# PDM_v1.net
KiCad netlist of a schematic drawn in EAGLE
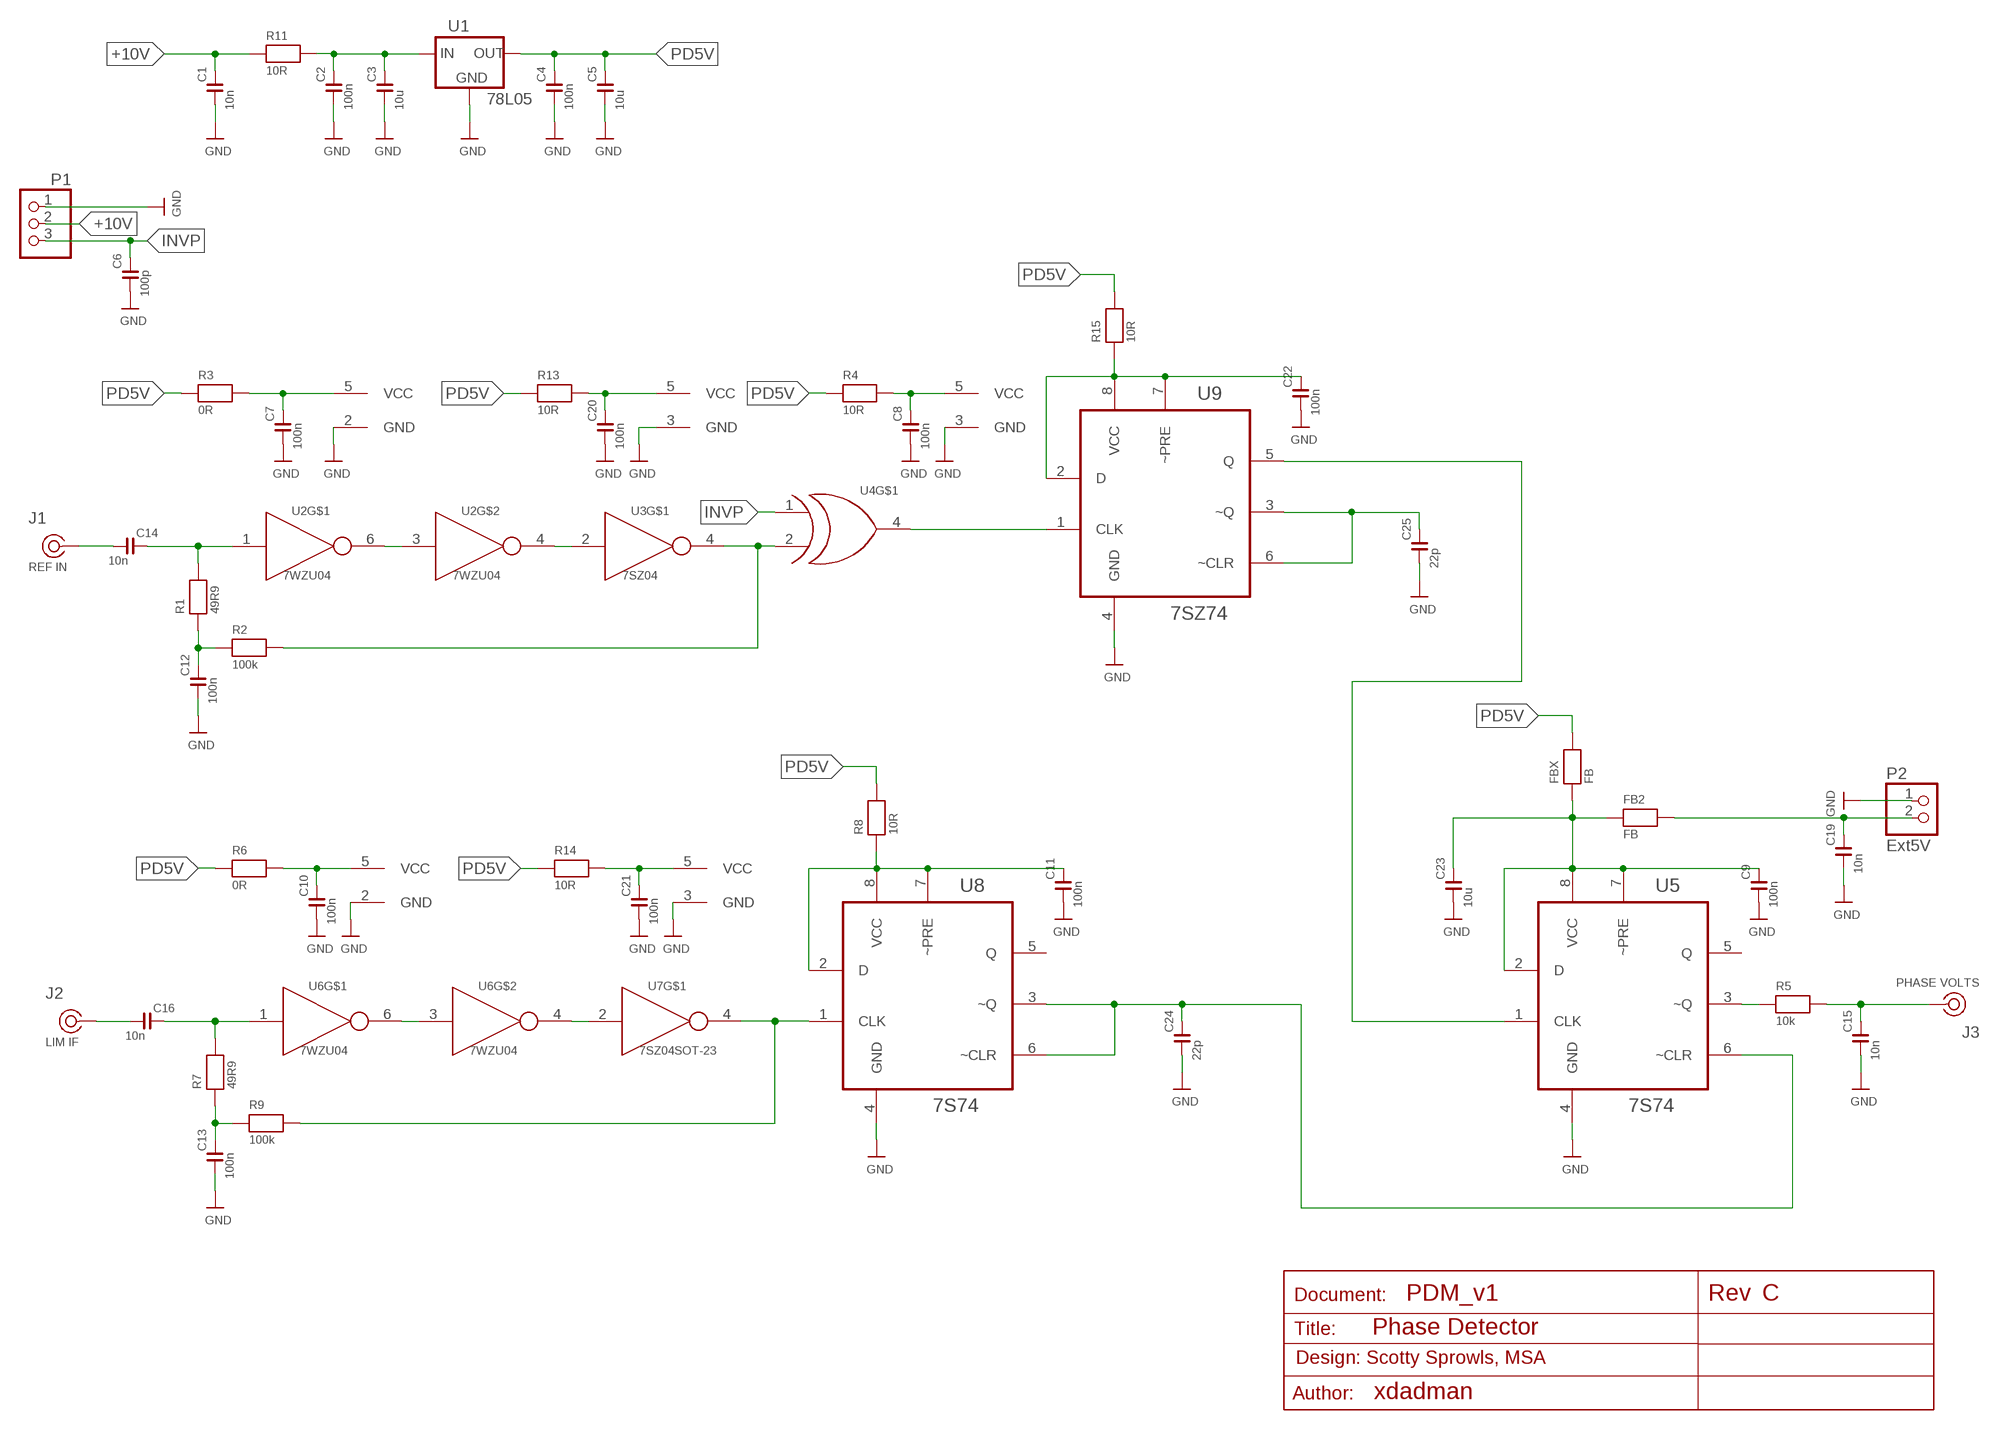
[diagram p0: schematic, sheet 1]

(export (version "E")
  (design (tool "Eeschema 10.0.6"))
  (components
    (comp (ref "C1")
      (value "10n")
      (footprint "eagle-import:C0805")
      (libsource (lib "eagle-import") (part "C080510N"))
    )
    (comp (ref "C2")
      (value "100n")
      (footprint "eagle-import:C0805")
      (libsource (lib "eagle-import") (part "C0805100N"))
    )
    (comp (ref "C3")
      (value "10u")
      (footprint "eagle-import:C1206")
      (libsource (lib "eagle-import") (part "CC120610U"))
    )
    (comp (ref "C4")
      (value "100n")
      (footprint "eagle-import:C0805")
      (libsource (lib "eagle-import") (part "C0805100N"))
    )
    (comp (ref "C5")
      (value "10u")
      (footprint "eagle-import:C1206")
      (libsource (lib "eagle-import") (part "CC120610U"))
    )
    (comp (ref "C6")
      (value "100p")
      (footprint "eagle-import:C0805")
      (libsource (lib "eagle-import") (part "C0805100P"))
    )
    (comp (ref "C7")
      (value "100n")
      (footprint "eagle-import:C0805")
      (libsource (lib "eagle-import") (part "C0805100N"))
    )
    (comp (ref "C8")
      (value "100n")
      (footprint "eagle-import:C0805")
      (libsource (lib "eagle-import") (part "C0805100N"))
    )
    (comp (ref "C9")
      (value "100n")
      (footprint "eagle-import:C0805")
      (libsource (lib "eagle-import") (part "C0805100N"))
    )
    (comp (ref "C10")
      (value "100n")
      (footprint "eagle-import:C0805")
      (libsource (lib "eagle-import") (part "C0805100N"))
    )
    (comp (ref "C11")
      (value "100n")
      (footprint "eagle-import:C0805")
      (libsource (lib "eagle-import") (part "C0805100N"))
    )
    (comp (ref "C12")
      (value "100n")
      (footprint "eagle-import:C0805")
      (libsource (lib "eagle-import") (part "C0805100N"))
    )
    (comp (ref "C13")
      (value "100n")
      (footprint "eagle-import:C0805")
      (libsource (lib "eagle-import") (part "C0805100N"))
    )
    (comp (ref "C14")
      (value "10n")
      (footprint "eagle-import:C0805")
      (libsource (lib "eagle-import") (part "C080510N"))
    )
    (comp (ref "C15")
      (value "10n")
      (footprint "eagle-import:C0805")
      (libsource (lib "eagle-import") (part "C080510N"))
    )
    (comp (ref "C16")
      (value "10n")
      (footprint "eagle-import:C0805")
      (libsource (lib "eagle-import") (part "C080510N"))
    )
    (comp (ref "C19")
      (value "10n")
      (footprint "eagle-import:C0805")
      (libsource (lib "eagle-import") (part "C080510N"))
    )
    (comp (ref "C20")
      (value "100n")
      (footprint "eagle-import:C0805")
      (libsource (lib "eagle-import") (part "C0805100N"))
    )
    (comp (ref "C21")
      (value "100n")
      (footprint "eagle-import:C0805")
      (libsource (lib "eagle-import") (part "C0805100N"))
    )
    (comp (ref "C22")
      (value "100n")
      (footprint "eagle-import:C0805")
      (libsource (lib "eagle-import") (part "C0805100N"))
    )
    (comp (ref "C23")
      (value "10u")
      (footprint "eagle-import:C1206")
      (libsource (lib "eagle-import") (part "CC120610U"))
    )
    (comp (ref "C24")
      (value "22p")
      (footprint "eagle-import:C0603")
      (libsource (lib "eagle-import") (part "CC060322P"))
    )
    (comp (ref "C25")
      (value "22p")
      (footprint "eagle-import:C0603")
      (libsource (lib "eagle-import") (part "CC060322P"))
    )
    (comp (ref "FB2")
      (value "FB")
      (footprint "eagle-import:R0805")
      (libsource (lib "eagle-import") (part "R0805FB045"))
    )
    (comp (ref "FBX")
      (value "FB")
      (footprint "eagle-import:R0805")
      (libsource (lib "eagle-import") (part "R0805FB045"))
    )
    (comp (ref "J1")
      (value "REF IN")
      (footprint "eagle-import:SLIM_COAX_PAD")
      (libsource (lib "eagle-import") (part "COAX"))
    )
    (comp (ref "J2")
      (value "LIM IF")
      (footprint "eagle-import:SLIM_COAX_PAD")
      (libsource (lib "eagle-import") (part "COAX"))
    )
    (comp (ref "J3")
      (value "PHASE VOLTS")
      (footprint "eagle-import:SLIM_COAX_PAD")
      (libsource (lib "eagle-import") (part "COAX"))
    )
    (comp (ref "P1")
      (value "PINHD-1X3")
      (footprint "eagle-import:1X03")
      (libsource (lib "eagle-import") (part "PINHD-1X3"))
    )
    (comp (ref "P2")
      (value "Ext5V")
      (footprint "eagle-import:1X02")
      (libsource (lib "eagle-import") (part "PINHD-1X2"))
    )
    (comp (ref "R1")
      (value "49R9")
      (footprint "eagle-import:R0805")
      (libsource (lib "eagle-import") (part "R080549R9"))
    )
    (comp (ref "R2")
      (value "100k")
      (footprint "eagle-import:R0805")
      (libsource (lib "eagle-import") (part "R0805100K"))
    )
    (comp (ref "R3")
      (value "0R")
      (footprint "eagle-import:R0805")
      (libsource (lib "eagle-import") (part "R08050R"))
    )
    (comp (ref "R4")
      (value "10R")
      (footprint "eagle-import:R0805")
      (libsource (lib "eagle-import") (part "R080510R"))
    )
    (comp (ref "R5")
      (value "10k")
      (footprint "eagle-import:R0805")
      (libsource (lib "eagle-import") (part "R080510K"))
    )
    (comp (ref "R6")
      (value "0R")
      (footprint "eagle-import:R0805")
      (libsource (lib "eagle-import") (part "R08050R"))
    )
    (comp (ref "R7")
      (value "49R9")
      (footprint "eagle-import:R0805")
      (libsource (lib "eagle-import") (part "R080549R9"))
    )
    (comp (ref "R8")
      (value "10R")
      (footprint "eagle-import:R0805")
      (libsource (lib "eagle-import") (part "R080510R"))
    )
    (comp (ref "R9")
      (value "100k")
      (footprint "eagle-import:R0805")
      (libsource (lib "eagle-import") (part "R0805100K"))
    )
    (comp (ref "R11")
      (value "10R")
      (footprint "eagle-import:R0805")
      (libsource (lib "eagle-import") (part "R080510R"))
    )
    (comp (ref "R13")
      (value "10R")
      (footprint "eagle-import:R0805")
      (libsource (lib "eagle-import") (part "R080510R"))
    )
    (comp (ref "R14")
      (value "10R")
      (footprint "eagle-import:R0805")
      (libsource (lib "eagle-import") (part "R080510R"))
    )
    (comp (ref "R15")
      (value "10R")
      (footprint "eagle-import:R0805")
      (libsource (lib "eagle-import") (part "R080510R"))
    )
    (comp (ref "U1")
      (value "78L05")
      (footprint "eagle-import:SOT89")
      (libsource (lib "eagle-import") (part "78MXXL78L05"))
    )
    (comp (ref "U2")
      (value "7WZU04")
      (footprint "eagle-import:SC70-6L")
      (libsource (lib "eagle-import") (part "7WZU04"))
    )
    (comp (ref "U3")
      (value "7SZ04")
      (footprint "eagle-import:SOT23-5L")
      (libsource (lib "eagle-import") (part "7SZ04SOT-23"))
    )
    (comp (ref "U4")
      (value "74LVC1G86")
      (footprint "eagle-import:SOT23-5L")
      (libsource (lib "eagle-import") (part "74LVC1G86"))
    )
    (comp (ref "U5")
      (value "7S74")
      (footprint "eagle-import:SOP50P310X90-8N")
      (fields (field (name "MPN") "SN74LVC2G74DCUR"))
      (libsource (lib "eagle-import") (part "SN74LVC2G74DCUR"))
    )
    (comp (ref "U6")
      (value "7WZU04")
      (footprint "eagle-import:SC70-6L")
      (libsource (lib "eagle-import") (part "7WZU04"))
    )
    (comp (ref "U7")
      (value "7SZ04SOT-23")
      (footprint "eagle-import:SOT23-5L")
      (libsource (lib "eagle-import") (part "7SZ04SOT-23"))
    )
    (comp (ref "U8")
      (value "7S74")
      (footprint "eagle-import:SOP50P310X90-8N")
      (fields (field (name "MPN") "SN74LVC2G74DCUR"))
      (libsource (lib "eagle-import") (part "SN74LVC2G74DCUR"))
    )
    (comp (ref "U9")
      (value "7SZ74")
      (footprint "eagle-import:SOP50P310X90-8N")
      (fields (field (name "MPN") "SN74LVC2G74DCUR"))
      (libsource (lib "eagle-import") (part "SN74LVC2G74DCUR"))
    )
  )
  (nets
    (net (code "1") (name "+10V") (class "Default")
      (node (ref "C1") (pin "2") (pinfunction "2_2") (pintype "passive"))
      (node (ref "P1") (pin "2") (pinfunction "2_2") (pintype "passive"))
      (node (ref "R11") (pin "1") (pinfunction "1_1") (pintype "passive"))
    )
    (net (code "2") (name "GND") (class "Default")
      (node (ref "C1") (pin "1") (pinfunction "1_1") (pintype "passive"))
      (node (ref "C10") (pin "1") (pinfunction "1_1") (pintype "passive"))
      (node (ref "C11") (pin "1") (pinfunction "1_1") (pintype "passive"))
      (node (ref "C12") (pin "1") (pinfunction "1_1") (pintype "passive"))
      (node (ref "C13") (pin "1") (pinfunction "1_1") (pintype "passive"))
      (node (ref "C15") (pin "1") (pinfunction "1_1") (pintype "passive"))
      (node (ref "C19") (pin "1") (pinfunction "1_1") (pintype "passive"))
      (node (ref "C2") (pin "1") (pinfunction "1_1") (pintype "passive"))
      (node (ref "C20") (pin "1") (pinfunction "1_1") (pintype "passive"))
      (node (ref "C21") (pin "1") (pinfunction "1_1") (pintype "passive"))
      (node (ref "C22") (pin "1") (pinfunction "1_1") (pintype "passive"))
      (node (ref "C23") (pin "1") (pinfunction "1_1") (pintype "passive"))
      (node (ref "C24") (pin "1") (pinfunction "1_1") (pintype "passive"))
      (node (ref "C25") (pin "1") (pinfunction "1_1") (pintype "passive"))
      (node (ref "C3") (pin "1") (pinfunction "1_1") (pintype "passive"))
      (node (ref "C4") (pin "1") (pinfunction "1_1") (pintype "passive"))
      (node (ref "C5") (pin "1") (pinfunction "1_1") (pintype "passive"))
      (node (ref "C6") (pin "1") (pinfunction "1_1") (pintype "passive"))
      (node (ref "C7") (pin "1") (pinfunction "1_1") (pintype "passive"))
      (node (ref "C8") (pin "1") (pinfunction "1_1") (pintype "passive"))
      (node (ref "C9") (pin "1") (pinfunction "1_1") (pintype "passive"))
      (node (ref "P1") (pin "1") (pinfunction "1_1") (pintype "passive"))
      (node (ref "P2") (pin "1") (pinfunction "1_1") (pintype "passive"))
      (node (ref "U1") (pin "2") (pinfunction "GND_2") (pintype "input"))
      (node (ref "U1") (pin "4") (pinfunction "GND_4") (pintype "input"))
      (node (ref "U2") (pin "2") (pinfunction "GND_2") (pintype "bidirectional"))
      (node (ref "U3") (pin "3") (pinfunction "GND_3") (pintype "bidirectional"))
      (node (ref "U4") (pin "3") (pinfunction "GND_3") (pintype "bidirectional"))
      (node (ref "U5") (pin "4") (pinfunction "GND_4") (pintype "passive"))
      (node (ref "U6") (pin "2") (pinfunction "GND_2") (pintype "bidirectional"))
      (node (ref "U7") (pin "3") (pinfunction "GND_3") (pintype "bidirectional"))
      (node (ref "U8") (pin "4") (pinfunction "GND_4") (pintype "passive"))
      (node (ref "U9") (pin "4") (pinfunction "GND_4") (pintype "passive"))
    )
    (net (code "3") (name "INVP") (class "Default")
      (node (ref "C6") (pin "2") (pinfunction "2_2") (pintype "passive"))
      (node (ref "P1") (pin "3") (pinfunction "3_3") (pintype "passive"))
      (node (ref "U4") (pin "1") (pinfunction "A_1") (pintype "bidirectional"))
    )
    (net (code "4") (name "Net-(C12-Pad2)") (class "Default")
      (node (ref "C12") (pin "2") (pinfunction "2_2") (pintype "passive"))
      (node (ref "R1") (pin "1") (pinfunction "1_1") (pintype "passive"))
      (node (ref "R2") (pin "1") (pinfunction "1_1") (pintype "passive"))
    )
    (net (code "5") (name "Net-(C13-Pad2)") (class "Default")
      (node (ref "C13") (pin "2") (pinfunction "2_2") (pintype "passive"))
      (node (ref "R7") (pin "1") (pinfunction "1_1") (pintype "passive"))
      (node (ref "R9") (pin "1") (pinfunction "1_1") (pintype "passive"))
    )
    (net (code "6") (name "Net-(C19-Pad2)") (class "Default")
      (node (ref "C19") (pin "2") (pinfunction "2_2") (pintype "passive"))
      (node (ref "FB2") (pin "2") (pinfunction "2_2") (pintype "passive"))
      (node (ref "P2") (pin "2") (pinfunction "2_2") (pintype "passive"))
    )
    (net (code "7") (name "Net-(J1A-1)") (class "Default")
      (node (ref "C14") (pin "1") (pinfunction "1_1") (pintype "passive"))
      (node (ref "J1") (pin "SIG") (pinfunction "1_SIG") (pintype "passive"))
    )
    (net (code "8") (name "Net-(J2A-1)") (class "Default")
      (node (ref "C16") (pin "1") (pinfunction "1_1") (pintype "passive"))
      (node (ref "J2") (pin "SIG") (pinfunction "1_SIG") (pintype "passive"))
    )
    (net (code "9") (name "Net-(J3A-1)") (class "Default")
      (node (ref "C15") (pin "2") (pinfunction "2_2") (pintype "passive"))
      (node (ref "J3") (pin "SIG") (pinfunction "1_SIG") (pintype "passive"))
      (node (ref "R5") (pin "2") (pinfunction "2_2") (pintype "passive"))
    )
    (net (code "10") (name "Net-(U1-IN)") (class "Default")
      (node (ref "C2") (pin "2") (pinfunction "2_2") (pintype "passive"))
      (node (ref "C3") (pin "2") (pinfunction "2_2") (pintype "passive"))
      (node (ref "R11") (pin "2") (pinfunction "2_2") (pintype "passive"))
      (node (ref "U1") (pin "3") (pinfunction "IN_3") (pintype "input"))
    )
    (net (code "11") (name "Net-(U2A-IN)") (class "Default")
      (node (ref "C14") (pin "2") (pinfunction "2_2") (pintype "passive"))
      (node (ref "R1") (pin "2") (pinfunction "2_2") (pintype "passive"))
      (node (ref "U2") (pin "1") (pinfunction "IN_1") (pintype "input"))
    )
    (net (code "12") (name "Net-(U2A-OUT)") (class "Default")
      (node (ref "U2") (pin "3") (pinfunction "IN_3") (pintype "input"))
      (node (ref "U2") (pin "6") (pinfunction "OUT_6") (pintype "output"))
    )
    (net (code "13") (name "Net-(U2B-OUT)") (class "Default")
      (node (ref "U2") (pin "4") (pinfunction "OUT_4") (pintype "output"))
      (node (ref "U3") (pin "2") (pinfunction "IN_2") (pintype "input"))
    )
    (net (code "14") (name "Net-(U2C-VCC)") (class "Default")
      (node (ref "C7") (pin "2") (pinfunction "2_2") (pintype "passive"))
      (node (ref "R3") (pin "2") (pinfunction "2_2") (pintype "passive"))
      (node (ref "U2") (pin "5") (pinfunction "VCC_5") (pintype "bidirectional"))
    )
    (net (code "15") (name "Net-(U3A-OUT)") (class "Default")
      (node (ref "R2") (pin "2") (pinfunction "2_2") (pintype "passive"))
      (node (ref "U3") (pin "4") (pinfunction "OUT_4") (pintype "output"))
      (node (ref "U4") (pin "2") (pinfunction "B_2") (pintype "bidirectional"))
    )
    (net (code "16") (name "Net-(U3B-VCC)") (class "Default")
      (node (ref "C20") (pin "2") (pinfunction "2_2") (pintype "passive"))
      (node (ref "R13") (pin "2") (pinfunction "2_2") (pintype "passive"))
      (node (ref "U3") (pin "5") (pinfunction "VCC_5") (pintype "bidirectional"))
    )
    (net (code "17") (name "Net-(U4A-Y)") (class "Default")
      (node (ref "U4") (pin "4") (pinfunction "Y_4") (pintype "bidirectional"))
      (node (ref "U9") (pin "1") (pinfunction "CLK_1") (pintype "input"))
    )
    (net (code "18") (name "Net-(U4B-VCC)") (class "Default")
      (node (ref "C8") (pin "2") (pinfunction "2_2") (pintype "passive"))
      (node (ref "R4") (pin "2") (pinfunction "2_2") (pintype "passive"))
      (node (ref "U4") (pin "5") (pinfunction "VCC_5") (pintype "bidirectional"))
    )
    (net (code "19") (name "Net-(U5-CLK)") (class "Default")
      (node (ref "U5") (pin "1") (pinfunction "CLK_1") (pintype "input"))
      (node (ref "U9") (pin "5") (pinfunction "Q_5") (pintype "output"))
    )
    (net (code "20") (name "Net-(U5-D)") (class "Default")
      (node (ref "C23") (pin "2") (pinfunction "2_2") (pintype "passive"))
      (node (ref "C9") (pin "2") (pinfunction "2_2") (pintype "passive"))
      (node (ref "FB2") (pin "1") (pinfunction "1_1") (pintype "passive"))
      (node (ref "FBX") (pin "1") (pinfunction "1_1") (pintype "passive"))
      (node (ref "U5") (pin "2") (pinfunction "D_2") (pintype "input"))
      (node (ref "U5") (pin "7") (pinfunction "~{PRE}_7") (pintype "input"))
      (node (ref "U5") (pin "8") (pinfunction "VCC_8") (pintype "power_in"))
    )
    (net (code "21") (name "Net-(U5-~{CLR})") (class "Default")
      (node (ref "C24") (pin "2") (pinfunction "2_2") (pintype "passive"))
      (node (ref "U5") (pin "6") (pinfunction "~{CLR}_6") (pintype "input"))
      (node (ref "U8") (pin "3") (pinfunction "~{Q}_3") (pintype "output"))
      (node (ref "U8") (pin "6") (pinfunction "~{CLR}_6") (pintype "input"))
    )
    (net (code "22") (name "Net-(U5-~{Q})") (class "Default")
      (node (ref "R5") (pin "1") (pinfunction "1_1") (pintype "passive"))
      (node (ref "U5") (pin "3") (pinfunction "~{Q}_3") (pintype "output"))
    )
    (net (code "23") (name "Net-(U6A-IN)") (class "Default")
      (node (ref "C16") (pin "2") (pinfunction "2_2") (pintype "passive"))
      (node (ref "R7") (pin "2") (pinfunction "2_2") (pintype "passive"))
      (node (ref "U6") (pin "1") (pinfunction "IN_1") (pintype "input"))
    )
    (net (code "24") (name "Net-(U6A-OUT)") (class "Default")
      (node (ref "U6") (pin "3") (pinfunction "IN_3") (pintype "input"))
      (node (ref "U6") (pin "6") (pinfunction "OUT_6") (pintype "output"))
    )
    (net (code "25") (name "Net-(U6B-OUT)") (class "Default")
      (node (ref "U6") (pin "4") (pinfunction "OUT_4") (pintype "output"))
      (node (ref "U7") (pin "2") (pinfunction "IN_2") (pintype "input"))
    )
    (net (code "26") (name "Net-(U6C-VCC)") (class "Default")
      (node (ref "C10") (pin "2") (pinfunction "2_2") (pintype "passive"))
      (node (ref "R6") (pin "2") (pinfunction "2_2") (pintype "passive"))
      (node (ref "U6") (pin "5") (pinfunction "VCC_5") (pintype "bidirectional"))
    )
    (net (code "27") (name "Net-(U7A-OUT)") (class "Default")
      (node (ref "R9") (pin "2") (pinfunction "2_2") (pintype "passive"))
      (node (ref "U7") (pin "4") (pinfunction "OUT_4") (pintype "output"))
      (node (ref "U8") (pin "1") (pinfunction "CLK_1") (pintype "input"))
    )
    (net (code "28") (name "Net-(U7B-VCC)") (class "Default")
      (node (ref "C21") (pin "2") (pinfunction "2_2") (pintype "passive"))
      (node (ref "R14") (pin "2") (pinfunction "2_2") (pintype "passive"))
      (node (ref "U7") (pin "5") (pinfunction "VCC_5") (pintype "bidirectional"))
    )
    (net (code "29") (name "Net-(U8-D)") (class "Default")
      (node (ref "C11") (pin "2") (pinfunction "2_2") (pintype "passive"))
      (node (ref "R8") (pin "1") (pinfunction "1_1") (pintype "passive"))
      (node (ref "U8") (pin "2") (pinfunction "D_2") (pintype "input"))
      (node (ref "U8") (pin "7") (pinfunction "~{PRE}_7") (pintype "input"))
      (node (ref "U8") (pin "8") (pinfunction "VCC_8") (pintype "power_in"))
    )
    (net (code "30") (name "Net-(U9-D)") (class "Default")
      (node (ref "C22") (pin "2") (pinfunction "2_2") (pintype "passive"))
      (node (ref "R15") (pin "1") (pinfunction "1_1") (pintype "passive"))
      (node (ref "U9") (pin "2") (pinfunction "D_2") (pintype "input"))
      (node (ref "U9") (pin "7") (pinfunction "~{PRE}_7") (pintype "input"))
      (node (ref "U9") (pin "8") (pinfunction "VCC_8") (pintype "power_in"))
    )
    (net (code "31") (name "Net-(U9-~{CLR})") (class "Default")
      (node (ref "C25") (pin "2") (pinfunction "2_2") (pintype "passive"))
      (node (ref "U9") (pin "3") (pinfunction "~{Q}_3") (pintype "output"))
      (node (ref "U9") (pin "6") (pinfunction "~{CLR}_6") (pintype "input"))
    )
    (net (code "32") (name "PD5V") (class "Default")
      (node (ref "C4") (pin "2") (pinfunction "2_2") (pintype "passive"))
      (node (ref "C5") (pin "2") (pinfunction "2_2") (pintype "passive"))
      (node (ref "FBX") (pin "2") (pinfunction "2_2") (pintype "passive"))
      (node (ref "R13") (pin "1") (pinfunction "1_1") (pintype "passive"))
      (node (ref "R14") (pin "1") (pinfunction "1_1") (pintype "passive"))
      (node (ref "R15") (pin "2") (pinfunction "2_2") (pintype "passive"))
      (node (ref "R3") (pin "1") (pinfunction "1_1") (pintype "passive"))
      (node (ref "R4") (pin "1") (pinfunction "1_1") (pintype "passive"))
      (node (ref "R6") (pin "1") (pinfunction "1_1") (pintype "passive"))
      (node (ref "R8") (pin "2") (pinfunction "2_2") (pintype "passive"))
      (node (ref "U1") (pin "1") (pinfunction "OUT_1") (pintype "passive"))
    )
    (net (code "33") (name "unconnected-(U5-Q-Pad5)") (class "Default")
      (node (ref "U5") (pin "5") (pinfunction "Q_5") (pintype "output"))
    )
    (net (code "34") (name "unconnected-(U8-Q-Pad5)") (class "Default")
      (node (ref "U8") (pin "5") (pinfunction "Q_5") (pintype "output"))
    )
  )
)
